# Adafruit_TMP117.net
KiCad netlist of a schematic drawn in EAGLE
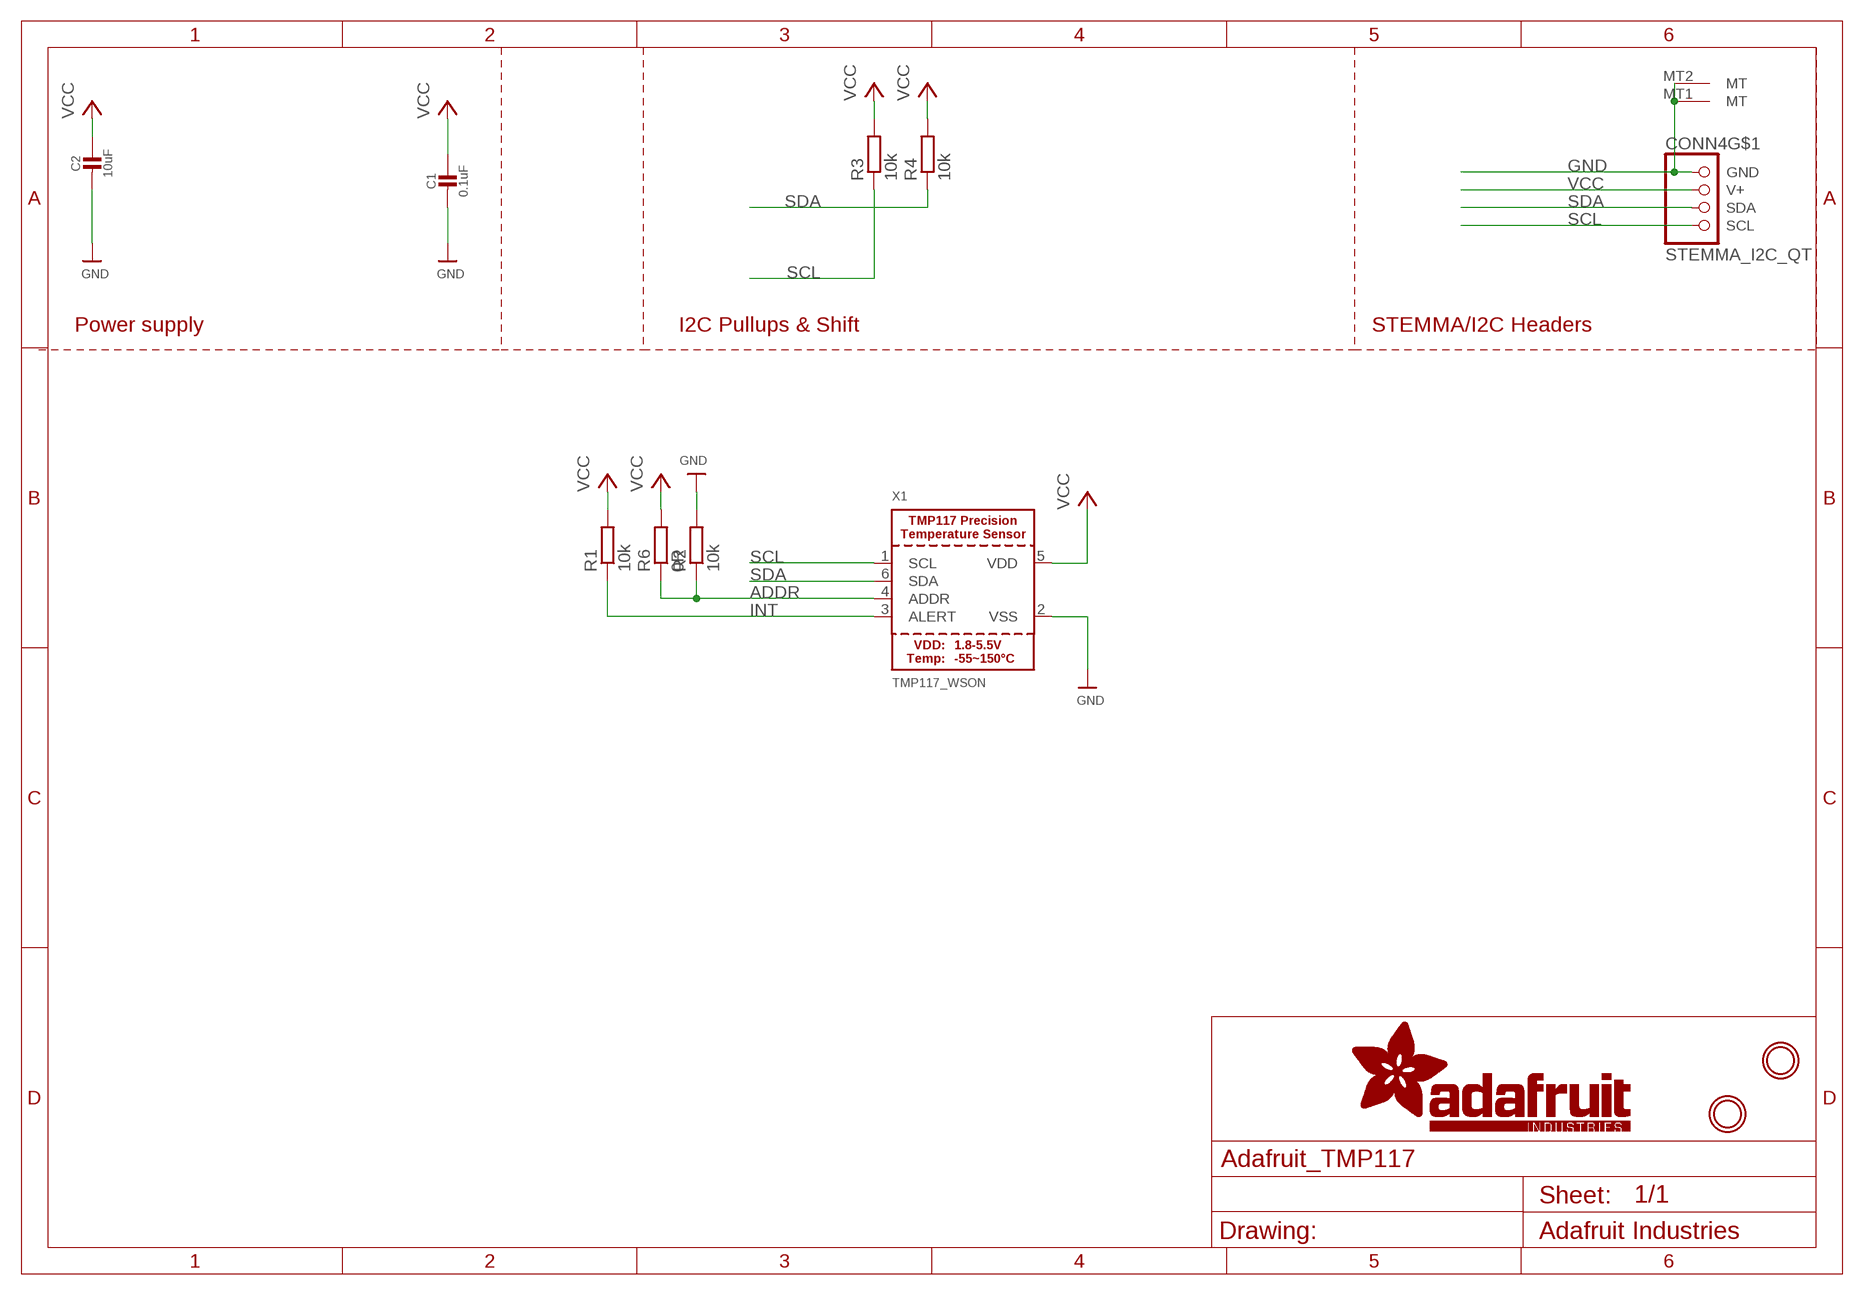
[diagram p0: schematic, sheet 1]

(export (version "E")
  (design (tool "Eeschema 10.0.6"))
  (components
    (comp (ref "C1")
      (value "0.1uF")
      (footprint "eagle-import:_0402")
      (libsource (lib "eagle-import") (part "CAP_CERAMIC_0402"))
    )
    (comp (ref "C2")
      (value "10uF")
      (footprint "eagle-import:_0603")
      (libsource (lib "eagle-import") (part "CAP_CERAMIC_0603"))
    )
    (comp (ref "CONN4")
      (value "STEMMA_I2C_QT")
      (footprint "eagle-import:JST_SH4")
      (libsource (lib "eagle-import") (part "STEMMA_I2C_QT"))
    )
    (comp (ref "R1")
      (value "10k")
      (footprint "eagle-import:R0402")
      (libsource (lib "eagle-import") (part "R-EU_R0402"))
    )
    (comp (ref "R2")
      (value "10k")
      (footprint "eagle-import:R0402")
      (libsource (lib "eagle-import") (part "R-EU_R0402"))
    )
    (comp (ref "R3")
      (value "10k")
      (footprint "eagle-import:R0402")
      (libsource (lib "eagle-import") (part "R-EU_R0402"))
    )
    (comp (ref "R4")
      (value "10k")
      (footprint "eagle-import:R0402")
      (libsource (lib "eagle-import") (part "R-EU_R0402"))
    )
    (comp (ref "R6")
      (value "0R")
      (footprint "eagle-import:R0402")
      (libsource (lib "eagle-import") (part "R-EU_R0402"))
    )
    (comp (ref "U$1")
      (value "MOUNTINGHOLE2.5")
      (footprint "eagle-import:MOUNTINGHOLE_2.5_PLATED")
      (libsource (lib "eagle-import") (part "MOUNTINGHOLE2.5"))
    )
    (comp (ref "U$19")
      (value "MOUNTINGHOLE2.5")
      (footprint "eagle-import:MOUNTINGHOLE_2.5_PLATED")
      (libsource (lib "eagle-import") (part "MOUNTINGHOLE2.5"))
    )
    (comp (ref "X1")
      (value "TMP117_WSON")
      (footprint "eagle-import:WSON-6")
      (libsource (lib "eagle-import") (part "TMP117_WSON"))
    )
  )
  (nets
    (net (code "1") (name "/ADDR") (class "Default")
      (node (ref "R2") (pin "1") (pinfunction "1_1") (pintype "passive"))
      (node (ref "R6") (pin "1") (pinfunction "1_1") (pintype "passive"))
      (node (ref "X1") (pin "4") (pinfunction "ADDR_4") (pintype "input"))
    )
    (net (code "2") (name "/INT") (class "Default")
      (node (ref "R1") (pin "1") (pinfunction "1_1") (pintype "passive"))
      (node (ref "X1") (pin "3") (pinfunction "ALERT_3") (pintype "output"))
    )
    (net (code "3") (name "/SCL") (class "Default")
      (node (ref "CONN4") (pin "4") (pinfunction "SCL_4") (pintype "passive"))
      (node (ref "R3") (pin "1") (pinfunction "1_1") (pintype "passive"))
      (node (ref "X1") (pin "1") (pinfunction "SCL_1") (pintype "bidirectional"))
    )
    (net (code "4") (name "/SDA") (class "Default")
      (node (ref "CONN4") (pin "3") (pinfunction "SDA_3") (pintype "passive"))
      (node (ref "R4") (pin "1") (pinfunction "1_1") (pintype "passive"))
      (node (ref "X1") (pin "6") (pinfunction "SDA_6") (pintype "bidirectional"))
    )
    (net (code "5") (name "GND") (class "Default")
      (node (ref "C1") (pin "2") (pinfunction "2_2") (pintype "passive"))
      (node (ref "C2") (pin "2") (pinfunction "2_2") (pintype "passive"))
      (node (ref "CONN4") (pin "1") (pinfunction "GND_1") (pintype "passive"))
      (node (ref "CONN4") (pin "MT1") (pinfunction "MT_MT1") (pintype "bidirectional"))
      (node (ref "CONN4") (pin "MT2") (pinfunction "MT_MT2") (pintype "bidirectional"))
      (node (ref "R2") (pin "2") (pinfunction "2_2") (pintype "passive"))
      (node (ref "X1") (pin "2") (pinfunction "VSS_2") (pintype "power_in"))
    )
    (net (code "6") (name "VCC") (class "Default")
      (node (ref "C1") (pin "1") (pinfunction "1_1") (pintype "passive"))
      (node (ref "C2") (pin "1") (pinfunction "1_1") (pintype "passive"))
      (node (ref "CONN4") (pin "2") (pinfunction "V+_2") (pintype "passive"))
      (node (ref "R1") (pin "2") (pinfunction "2_2") (pintype "passive"))
      (node (ref "R3") (pin "2") (pinfunction "2_2") (pintype "passive"))
      (node (ref "R4") (pin "2") (pinfunction "2_2") (pintype "passive"))
      (node (ref "R6") (pin "2") (pinfunction "2_2") (pintype "passive"))
      (node (ref "X1") (pin "5") (pinfunction "VDD_5") (pintype "power_in"))
    )
  )
)
